# OverlayConnection.net
KiCad netlist of a schematic drawn in Altium Designer
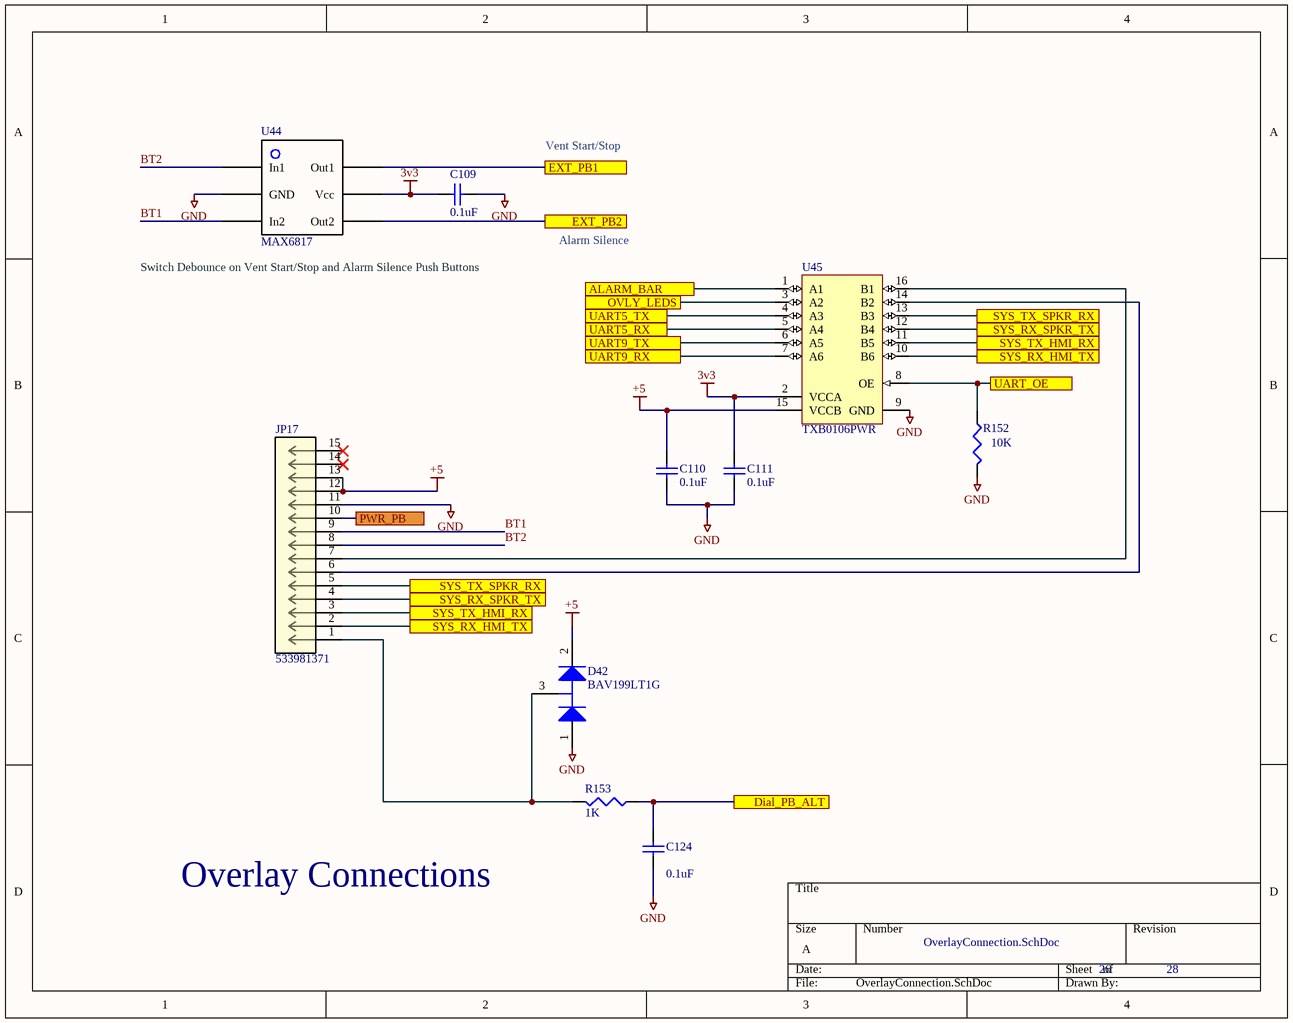
[diagram p0: OverlayConnection.SchDoc]

(export (version "E")
  (design (tool "Eeschema 10.0.6"))
  (components
    (comp (ref "C109")
      (value "0.1uF")
      (footprint "J1-0603")
      (description "Capacitor (Semiconductor SIM Model)")
      (fields
        (field (name "PARTNUMBER") "CL10F104ZO8NNNC")
        (field (name "MANUFACTURER") "Samsung")
        (field (name "PUBLISHER") "Altium Limited")
      )
      (libsource (lib "Miscellaneous Devices") (part "Cap Semi"))
    )
    (comp (ref "C110")
      (value "0.1uF")
      (footprint "J1-0603")
      (description "Capacitor (Semiconductor SIM Model)")
      (fields
        (field (name "PARTNUMBER") "CL10F104ZO8NNNC")
        (field (name "MANUFACTURER") "Samsung")
        (field (name "PUBLISHER") "Altium Limited")
      )
      (libsource (lib "Miscellaneous Devices") (part "Cap Semi"))
    )
    (comp (ref "C111")
      (value "0.1uF")
      (footprint "J1-0603")
      (description "Capacitor (Semiconductor SIM Model)")
      (fields
        (field (name "PARTNUMBER") "CL10F104ZO8NNNC")
        (field (name "MANUFACTURER") "Samsung")
        (field (name "PUBLISHER") "Altium Limited")
      )
      (libsource (lib "Miscellaneous Devices") (part "Cap Semi"))
    )
    (comp (ref "C124")
      (value "0.1uF")
      (footprint "J1-0603")
      (description "Capacitor (Semiconductor SIM Model)")
      (fields
        (field (name "PARTNUMBER") "CL10F104ZO8NNNC")
        (field (name "MANUFACTURER") "Samsung")
        (field (name "PUBLISHER") "Altium Limited")
      )
      (libsource (lib "Miscellaneous Devices") (part "Cap Semi"))
    )
    (comp (ref "D42")
      (value "BAV199LT1G")
      (footprint "ONSC-SOT-23-3-318-08_V")
      (description "Dual Series Switching Diodes, 3-Pin SOT-23, Pb-Free, Tape and Reel")
      (fields (field (name "MANUFACTURER") "On Semiconductor"))
      (libsource (lib "Altium Content Vault") (part "ONSC-D-A1K2C3-3"))
    )
    (comp (ref "JP17")
      (value "533981371")
      (footprint "533981371")
      (description "No Description Available")
      (fields
        (field (name "PARTNUMBER") "0533981371")
        (field (name "MANUFACTURER") "Molex")
        (field (name "COPYRIGHT") "Copyright (C) 2018 Accelerated Designs. All rights reserved")
      )
      (libsource (lib "0533981371") (part "533981371"))
    )
    (comp (ref "R152")
      (value "10K")
      (footprint "J1-0603")
      (description "Resistor")
      (fields
        (field (name "PARTNUMBER") "RC0603JR-0710KL")
        (field (name "MANUFACTURER") "Yageo")
        (field (name "PUBLISHER") "Altium Limited")
      )
      (libsource (lib "Miscellaneous Devices") (part "Res3"))
    )
    (comp (ref "R153")
      (value "1K")
      (footprint "J1-0603")
      (description "Resistor")
      (fields
        (field (name "PARTNUMBER") "RC0603JR-071KL")
        (field (name "MANUFACTURER") "Yageo")
        (field (name "PUBLISHER") "Altium Limited")
      )
      (libsource (lib "Miscellaneous Devices") (part "Res3"))
    )
    (comp (ref "U44")
      (value "MAX6817")
      (footprint "SOT23-6")
      (fields (field (name "PARTNUMBER") "MAX6817EUT+T") (field (name "MANUFACTURER") "Maxim Integrated"))
      (libsource (lib "MAX6817") (part "MAX6817"))
    )
    (comp (ref "U45")
      (value "TXB0106PWR")
      (footprint "PW0016A_L")
      (fields (field (name "MANUFACTURER") "Texas Instruments"))
      (libsource (lib "Altium Content Vault") (part "TI-TXB0106-TSSOP_PW-16"))
    )
  )
  (nets
    (net (code "1") (name "+5") (class "Default")
      (node (ref "C110") (pin "1") (pinfunction "1_1") (pintype "passive"))
      (node (ref "D42") (pin "2") (pinfunction "K_2") (pintype "passive"))
      (node (ref "JP17") (pin "12") (pinfunction "12_12") (pintype "passive"))
      (node (ref "JP17") (pin "13") (pinfunction "13_13") (pintype "passive"))
      (node (ref "U45") (pin "15") (pinfunction "VCCB_15") (pintype "power_in"))
    )
    (net (code "2") (name "/ALARM_BAR") (class "Default")
      (node (ref "U45") (pin "1") (pinfunction "A1_1") (pintype "bidirectional"))
    )
    (net (code "3") (name "/BT1") (class "Default")
      (node (ref "JP17") (pin "9") (pinfunction "9_9") (pintype "passive"))
      (node (ref "U44") (pin "3") (pinfunction "In2_3") (pintype "passive"))
    )
    (net (code "4") (name "/BT2") (class "Default")
      (node (ref "JP17") (pin "8") (pinfunction "8_8") (pintype "passive"))
      (node (ref "U44") (pin "1") (pinfunction "In1_1") (pintype "passive"))
    )
    (net (code "5") (name "/Dial_PB_ALT") (class "Default")
      (node (ref "C124") (pin "2") (pinfunction "2_2") (pintype "passive"))
      (node (ref "R153") (pin "1") (pinfunction "1_1") (pintype "passive"))
    )
    (net (code "6") (name "/EXT_PB1") (class "Default")
      (node (ref "U44") (pin "6") (pinfunction "Out1_6") (pintype "passive"))
    )
    (net (code "7") (name "/EXT_PB2") (class "Default")
      (node (ref "U44") (pin "4") (pinfunction "Out2_4") (pintype "passive"))
    )
    (net (code "8") (name "/OVLY_LEDS") (class "Default")
      (node (ref "U45") (pin "3") (pinfunction "A2_3") (pintype "bidirectional"))
    )
    (net (code "9") (name "/PWR_PB") (class "Default")
      (node (ref "JP17") (pin "10") (pinfunction "10_10") (pintype "passive"))
    )
    (net (code "10") (name "/SYS_RX_HMI_TX") (class "Default")
      (node (ref "JP17") (pin "2") (pinfunction "2_2") (pintype "passive"))
      (node (ref "U45") (pin "10") (pinfunction "B6_10") (pintype "bidirectional"))
    )
    (net (code "11") (name "/SYS_RX_SPKR_TX") (class "Default")
      (node (ref "JP17") (pin "4") (pinfunction "4_4") (pintype "passive"))
      (node (ref "U45") (pin "12") (pinfunction "B4_12") (pintype "bidirectional"))
    )
    (net (code "12") (name "/SYS_TX_HMI_RX") (class "Default")
      (node (ref "JP17") (pin "3") (pinfunction "3_3") (pintype "passive"))
      (node (ref "U45") (pin "11") (pinfunction "B5_11") (pintype "bidirectional"))
    )
    (net (code "13") (name "/SYS_TX_SPKR_RX") (class "Default")
      (node (ref "JP17") (pin "5") (pinfunction "5_5") (pintype "passive"))
      (node (ref "U45") (pin "13") (pinfunction "B3_13") (pintype "bidirectional"))
    )
    (net (code "14") (name "/UART5_RX") (class "Default")
      (node (ref "U45") (pin "5") (pinfunction "A4_5") (pintype "bidirectional"))
    )
    (net (code "15") (name "/UART5_TX") (class "Default")
      (node (ref "U45") (pin "4") (pinfunction "A3_4") (pintype "bidirectional"))
    )
    (net (code "16") (name "/UART9_RX") (class "Default")
      (node (ref "U45") (pin "7") (pinfunction "A6_7") (pintype "bidirectional"))
    )
    (net (code "17") (name "/UART9_TX") (class "Default")
      (node (ref "U45") (pin "6") (pinfunction "A5_6") (pintype "bidirectional"))
    )
    (net (code "18") (name "/UART_OE") (class "Default")
      (node (ref "R152") (pin "1") (pinfunction "1_1") (pintype "passive"))
      (node (ref "U45") (pin "8") (pinfunction "OE_8") (pintype "input"))
    )
    (net (code "19") (name "3v3") (class "Default")
      (node (ref "C109") (pin "2") (pinfunction "2_2") (pintype "passive"))
      (node (ref "C111") (pin "1") (pinfunction "1_1") (pintype "passive"))
      (node (ref "U44") (pin "5") (pinfunction "Vcc_5") (pintype "passive"))
      (node (ref "U45") (pin "2") (pinfunction "VCCA_2") (pintype "power_in"))
    )
    (net (code "20") (name "GND") (class "Default")
      (node (ref "C109") (pin "1") (pinfunction "1_1") (pintype "passive"))
      (node (ref "C110") (pin "2") (pinfunction "2_2") (pintype "passive"))
      (node (ref "C111") (pin "2") (pinfunction "2_2") (pintype "passive"))
      (node (ref "C124") (pin "1") (pinfunction "1_1") (pintype "passive"))
      (node (ref "D42") (pin "1") (pinfunction "A_1") (pintype "passive"))
      (node (ref "JP17") (pin "11") (pinfunction "11_11") (pintype "passive"))
      (node (ref "R152") (pin "2") (pinfunction "2_2") (pintype "passive"))
      (node (ref "U44") (pin "2") (pinfunction "GND_2") (pintype "passive"))
      (node (ref "U45") (pin "9") (pinfunction "GND_9") (pintype "power_in"))
    )
    (net (code "21") (name "Net-(D42-K{slash}A)") (class "Default")
      (node (ref "D42") (pin "3") (pinfunction "K/A_3") (pintype "passive"))
      (node (ref "JP17") (pin "1") (pinfunction "1_1") (pintype "passive"))
      (node (ref "R153") (pin "2") (pinfunction "2_2") (pintype "passive"))
    )
    (net (code "22") (name "Net-(U45-B1)") (class "Default")
      (node (ref "JP17") (pin "7") (pinfunction "7_7") (pintype "passive"))
      (node (ref "U45") (pin "16") (pinfunction "B1_16") (pintype "bidirectional"))
    )
    (net (code "23") (name "Net-(U45-B2)") (class "Default")
      (node (ref "JP17") (pin "6") (pinfunction "6_6") (pintype "passive"))
      (node (ref "U45") (pin "14") (pinfunction "B2_14") (pintype "bidirectional"))
    )
    (net (code "24") (name "unconnected-(JP17-Pad14)") (class "Default")
      (node (ref "JP17") (pin "14") (pinfunction "14_14") (pintype "passive+no_connect"))
    )
    (net (code "25") (name "unconnected-(JP17-Pad15)") (class "Default")
      (node (ref "JP17") (pin "15") (pinfunction "15_15") (pintype "passive+no_connect"))
    )
  )
)
